# Sheet1.net
KiCad netlist of a schematic drawn in Altium Designer
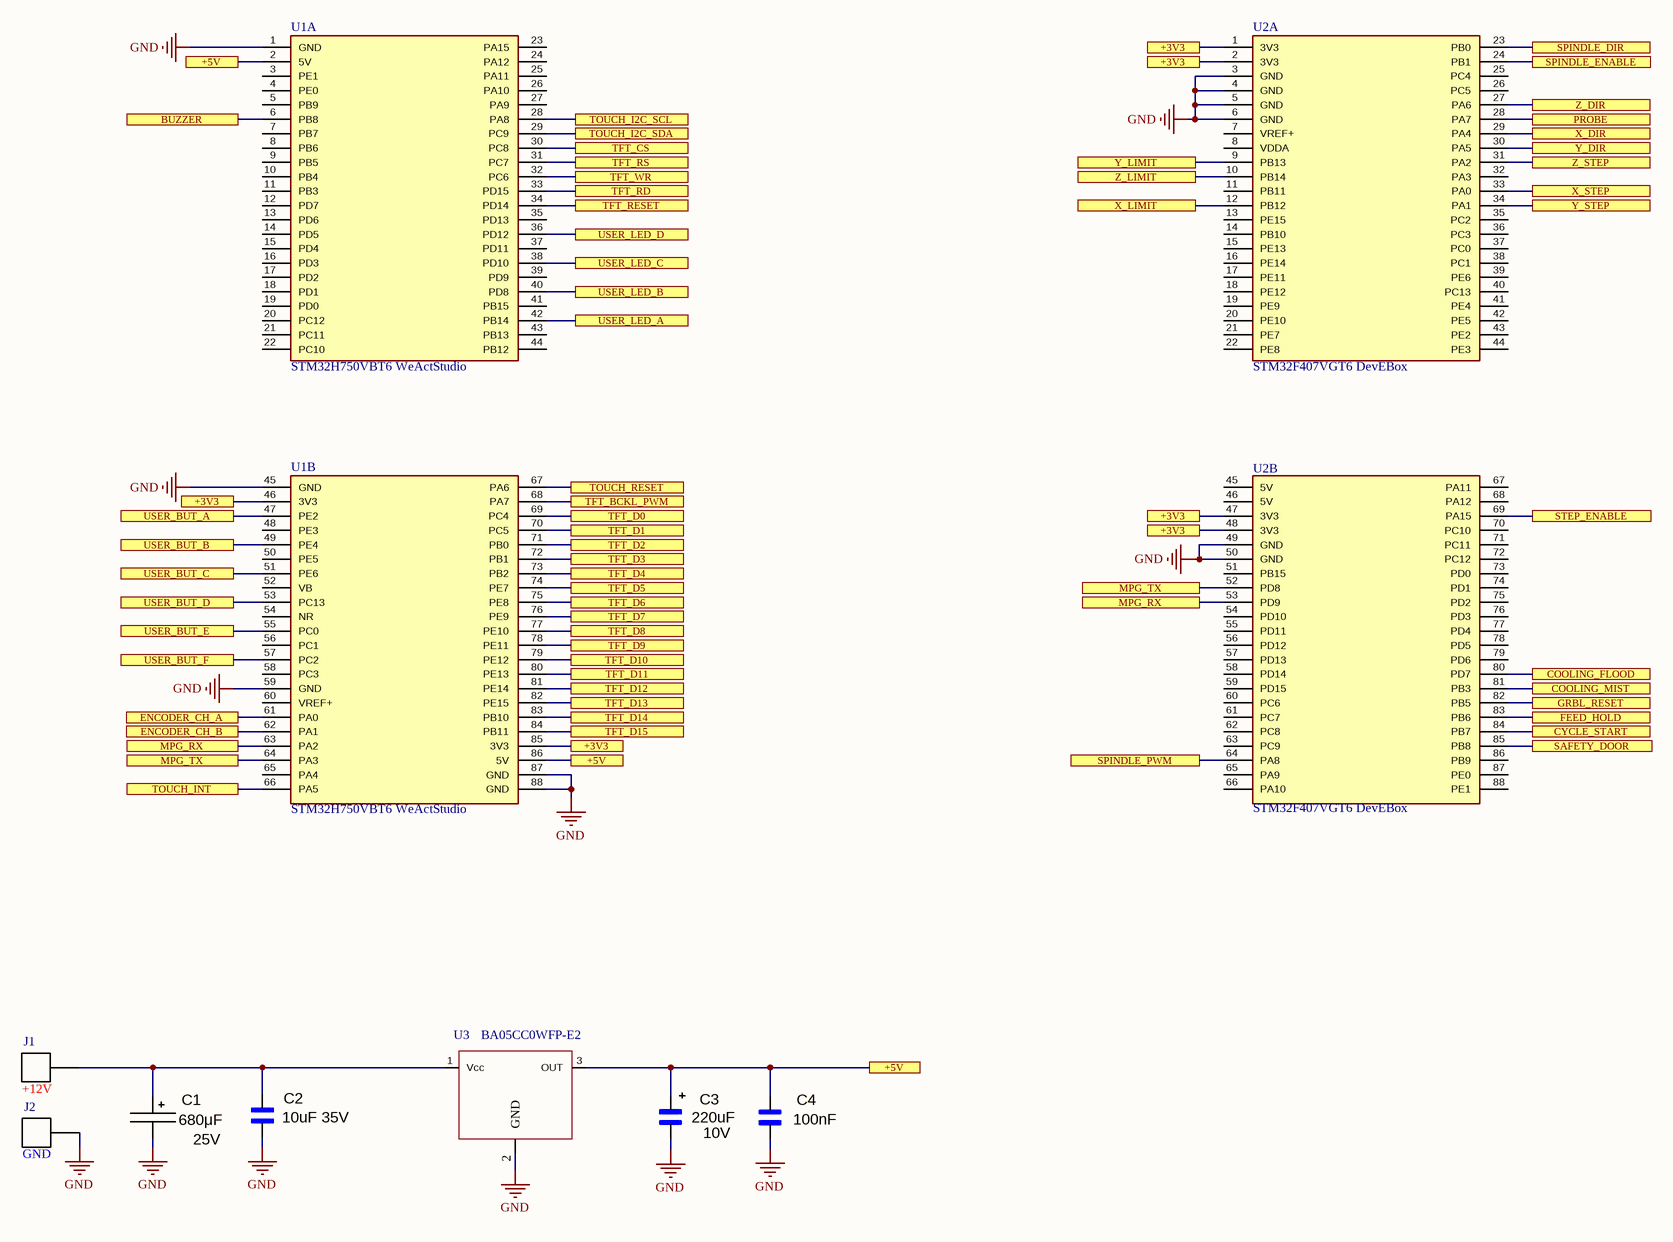
[diagram p0: Sheet1.SchDoc]

(export (version "E")
  (design (tool "Eeschema 10.0.6"))
  (components
    (comp (ref "C1")
      (value "680μF")
      (footprint "CAP 10x16")
      (fields
        (field (name "MANUFACTURER") "FUJICON")
        (field (name "VOLTAGE") "25V")
        (field (name "Comment") "680μF / 25V")
      )
      (libsource (lib "CAN_Library") (part "CAP Aluminium"))
    )
    (comp (ref "C2")
      (value "10uF 35V")
      (footprint "*CAPC3326X230N")
      (description "C1210 10uF 35V X7R")
      (fields (field (name "MANUFACTURER") "SAMSUNG ELECTRO-MECHANICS") (field (name "VOLTAGE") " 35V"))
      (libsource (lib "CAN_Library") (part "CL32B106KLJNNNE"))
    )
    (comp (ref "C3")
      (value "220uF")
      (footprint "SMD 7343-43")
      (description "Cap Tant Solid 220uF 10V E CASE 10% _7.3 X 4.3 X 4mm_ SMD 7343-43 0.1 Ohm 125В°C T/R")
      (fields (field (name "MANUFACTURER") "VISHAY") (field (name "VOLTAGE") "10V"))
      (libsource (lib "CAN_Library") (part "Cap Tant 220uF 10V Case E"))
    )
    (comp (ref "C4")
      (value "100nF")
      (footprint "SMD 0603")
      (description "C1210 10uF 35V X7R")
      (fields (field (name "MANUFACTURER") "SAMSUNG ELECTRO-MECHANICS"))
      (libsource (lib "CAN_Library") (part "CL32B106KLJNNNE"))
    )
    (comp (ref "J1")
      (value "+12V")
      (footprint "Wire")
      (description "Wire")
      (libsource (lib "CAN_Library") (part "Wire"))
    )
    (comp (ref "J2")
      (value "GND")
      (footprint "Wire")
      (description "Wire")
      (libsource (lib "CAN_Library") (part "Wire"))
    )
    (comp (ref "U1")
      (value "STM32H750VBT6 WeActStudio")
      (footprint "WeActStudio STM32H750VBT6")
      (libsource (lib "CAN_Library") (part "STM32H750VBT6 WeActStudio"))
    )
    (comp (ref "U2")
      (value "STM32F407VGT6 DevEBox")
      (footprint "DevEBox V3.0 STM32F407VGT6")
      (libsource (lib "CAN_Library") (part "STM32F407VGT6 DevEBox"))
    )
    (comp (ref "U3")
      (value "BA05CC0WFP-E2")
      (footprint "DPAK228P968X238-4N")
      (description "LDO Regulator")
      (fields (field (name "MANUFACTURER") "ROHM Semiconductor"))
      (libsource (lib "CAN_Library") (part "BA05CC0FP-E2"))
    )
  )
  (nets
    (net (code "1") (name "/+3V3") (class "Default")
      (node (ref "U1") (pin "46") (pinfunction "3V3_46") (pintype "passive"))
      (node (ref "U1") (pin "85") (pinfunction "3V3_85") (pintype "passive"))
      (node (ref "U2") (pin "1") (pinfunction "3V3_1") (pintype "passive"))
      (node (ref "U2") (pin "2") (pinfunction "3V3_2") (pintype "passive"))
      (node (ref "U2") (pin "47") (pinfunction "3V3_47") (pintype "passive"))
      (node (ref "U2") (pin "48") (pinfunction "3V3_48") (pintype "passive"))
    )
    (net (code "2") (name "/+5V") (class "Default")
      (node (ref "C3") (pin "1") (pinfunction "1_1") (pintype "passive"))
      (node (ref "C4") (pin "2") (pinfunction "2_2") (pintype "passive"))
      (node (ref "U1") (pin "2") (pinfunction "5V_2") (pintype "passive"))
      (node (ref "U1") (pin "86") (pinfunction "5V_86") (pintype "passive"))
      (node (ref "U3") (pin "3") (pinfunction "OUT_3") (pintype "passive"))
    )
    (net (code "3") (name "/BUZZER") (class "Default")
      (node (ref "U1") (pin "6") (pinfunction "PB8_6") (pintype "passive"))
    )
    (net (code "4") (name "/COOLING_FLOOD") (class "Default")
      (node (ref "U2") (pin "80") (pinfunction "PD7_80") (pintype "passive"))
    )
    (net (code "5") (name "/COOLING_MIST") (class "Default")
      (node (ref "U2") (pin "81") (pinfunction "PB3_81") (pintype "passive"))
    )
    (net (code "6") (name "/CYCLE_START") (class "Default")
      (node (ref "U2") (pin "84") (pinfunction "PB7_84") (pintype "passive"))
    )
    (net (code "7") (name "/ENCODER_CH_A") (class "Default")
      (node (ref "U1") (pin "61") (pinfunction "PA0_61") (pintype "passive"))
    )
    (net (code "8") (name "/ENCODER_CH_B") (class "Default")
      (node (ref "U1") (pin "62") (pinfunction "PA1_62") (pintype "passive"))
    )
    (net (code "9") (name "/FEED_HOLD") (class "Default")
      (node (ref "U2") (pin "83") (pinfunction "PB6_83") (pintype "passive"))
    )
    (net (code "10") (name "/GRBL_RESET") (class "Default")
      (node (ref "U2") (pin "82") (pinfunction "PB5_82") (pintype "passive"))
    )
    (net (code "11") (name "/MPG_RX") (class "Default")
      (node (ref "U1") (pin "63") (pinfunction "PA2_63") (pintype "passive"))
      (node (ref "U2") (pin "53") (pinfunction "PD9_53") (pintype "passive"))
    )
    (net (code "12") (name "/MPG_TX") (class "Default")
      (node (ref "U1") (pin "64") (pinfunction "PA3_64") (pintype "passive"))
      (node (ref "U2") (pin "52") (pinfunction "PD8_52") (pintype "passive"))
    )
    (net (code "13") (name "/PROBE") (class "Default")
      (node (ref "U2") (pin "28") (pinfunction "PA7_28") (pintype "passive"))
    )
    (net (code "14") (name "/SAFETY_DOOR") (class "Default")
      (node (ref "U2") (pin "85") (pinfunction "PB8_85") (pintype "passive"))
    )
    (net (code "15") (name "/SPINDLE_DIR") (class "Default")
      (node (ref "U2") (pin "23") (pinfunction "PB0_23") (pintype "passive"))
    )
    (net (code "16") (name "/SPINDLE_ENABLE") (class "Default")
      (node (ref "U2") (pin "24") (pinfunction "PB1_24") (pintype "passive"))
    )
    (net (code "17") (name "/SPINDLE_PWM") (class "Default")
      (node (ref "U2") (pin "64") (pinfunction "PA8_64") (pintype "passive"))
    )
    (net (code "18") (name "/STEP_ENABLE") (class "Default")
      (node (ref "U2") (pin "69") (pinfunction "PA15_69") (pintype "passive"))
    )
    (net (code "19") (name "/TFT_BCKL_PWM") (class "Default")
      (node (ref "U1") (pin "68") (pinfunction "PA7_68") (pintype "passive"))
    )
    (net (code "20") (name "/TFT_CS") (class "Default")
      (node (ref "U1") (pin "30") (pinfunction "PC8_30") (pintype "passive"))
    )
    (net (code "21") (name "/TFT_D0") (class "Default")
      (node (ref "U1") (pin "69") (pinfunction "PC4_69") (pintype "passive"))
    )
    (net (code "22") (name "/TFT_D1") (class "Default")
      (node (ref "U1") (pin "70") (pinfunction "PC5_70") (pintype "passive"))
    )
    (net (code "23") (name "/TFT_D2") (class "Default")
      (node (ref "U1") (pin "71") (pinfunction "PB0_71") (pintype "passive"))
    )
    (net (code "24") (name "/TFT_D3") (class "Default")
      (node (ref "U1") (pin "72") (pinfunction "PB1_72") (pintype "passive"))
    )
    (net (code "25") (name "/TFT_D4") (class "Default")
      (node (ref "U1") (pin "73") (pinfunction "PB2_73") (pintype "passive"))
    )
    (net (code "26") (name "/TFT_D5") (class "Default")
      (node (ref "U1") (pin "74") (pinfunction "PE7_74") (pintype "passive"))
    )
    (net (code "27") (name "/TFT_D6") (class "Default")
      (node (ref "U1") (pin "75") (pinfunction "PE8_75") (pintype "passive"))
    )
    (net (code "28") (name "/TFT_D7") (class "Default")
      (node (ref "U1") (pin "76") (pinfunction "PE9_76") (pintype "passive"))
    )
    (net (code "29") (name "/TFT_D8") (class "Default")
      (node (ref "U1") (pin "77") (pinfunction "PE10_77") (pintype "passive"))
    )
    (net (code "30") (name "/TFT_D9") (class "Default")
      (node (ref "U1") (pin "78") (pinfunction "PE11_78") (pintype "passive"))
    )
    (net (code "31") (name "/TFT_D10") (class "Default")
      (node (ref "U1") (pin "79") (pinfunction "PE12_79") (pintype "passive"))
    )
    (net (code "32") (name "/TFT_D11") (class "Default")
      (node (ref "U1") (pin "80") (pinfunction "PE13_80") (pintype "passive"))
    )
    (net (code "33") (name "/TFT_D12") (class "Default")
      (node (ref "U1") (pin "81") (pinfunction "PE14_81") (pintype "passive"))
    )
    (net (code "34") (name "/TFT_D13") (class "Default")
      (node (ref "U1") (pin "82") (pinfunction "PE15_82") (pintype "passive"))
    )
    (net (code "35") (name "/TFT_D14") (class "Default")
      (node (ref "U1") (pin "83") (pinfunction "PB10_83") (pintype "passive"))
    )
    (net (code "36") (name "/TFT_D15") (class "Default")
      (node (ref "U1") (pin "84") (pinfunction "PB11_84") (pintype "passive"))
    )
    (net (code "37") (name "/TFT_RD") (class "Default")
      (node (ref "U1") (pin "33") (pinfunction "PD15_33") (pintype "passive"))
    )
    (net (code "38") (name "/TFT_RESET") (class "Default")
      (node (ref "U1") (pin "34") (pinfunction "PD14_34") (pintype "passive"))
    )
    (net (code "39") (name "/TFT_RS") (class "Default")
      (node (ref "U1") (pin "31") (pinfunction "PC7_31") (pintype "passive"))
    )
    (net (code "40") (name "/TFT_WR") (class "Default")
      (node (ref "U1") (pin "32") (pinfunction "PC6_32") (pintype "passive"))
    )
    (net (code "41") (name "/TOUCH_I2C_SCL") (class "Default")
      (node (ref "U1") (pin "28") (pinfunction "PA8_28") (pintype "passive"))
    )
    (net (code "42") (name "/TOUCH_I2C_SDA") (class "Default")
      (node (ref "U1") (pin "29") (pinfunction "PC9_29") (pintype "passive"))
    )
    (net (code "43") (name "/TOUCH_INT") (class "Default")
      (node (ref "U1") (pin "66") (pinfunction "PA5_66") (pintype "passive"))
    )
    (net (code "44") (name "/TOUCH_RESET") (class "Default")
      (node (ref "U1") (pin "67") (pinfunction "PA6_67") (pintype "passive"))
    )
    (net (code "45") (name "/USER_BUT_A") (class "Default")
      (node (ref "U1") (pin "47") (pinfunction "PE2_47") (pintype "passive"))
    )
    (net (code "46") (name "/USER_BUT_B") (class "Default")
      (node (ref "U1") (pin "49") (pinfunction "PE4_49") (pintype "passive"))
    )
    (net (code "47") (name "/USER_BUT_C") (class "Default")
      (node (ref "U1") (pin "51") (pinfunction "PE6_51") (pintype "passive"))
    )
    (net (code "48") (name "/USER_BUT_D") (class "Default")
      (node (ref "U1") (pin "53") (pinfunction "PC13_53") (pintype "passive"))
    )
    (net (code "49") (name "/USER_BUT_E") (class "Default")
      (node (ref "U1") (pin "55") (pinfunction "PC0_55") (pintype "passive"))
    )
    (net (code "50") (name "/USER_BUT_F") (class "Default")
      (node (ref "U1") (pin "57") (pinfunction "PC2_57") (pintype "passive"))
    )
    (net (code "51") (name "/USER_LED_A") (class "Default")
      (node (ref "U1") (pin "42") (pinfunction "PB14_42") (pintype "passive"))
    )
    (net (code "52") (name "/USER_LED_B") (class "Default")
      (node (ref "U1") (pin "40") (pinfunction "PD8_40") (pintype "passive"))
    )
    (net (code "53") (name "/USER_LED_C") (class "Default")
      (node (ref "U1") (pin "38") (pinfunction "PD10_38") (pintype "passive"))
    )
    (net (code "54") (name "/USER_LED_D") (class "Default")
      (node (ref "U1") (pin "36") (pinfunction "PD12_36") (pintype "passive"))
    )
    (net (code "55") (name "/X_DIR") (class "Default")
      (node (ref "U2") (pin "29") (pinfunction "PA4_29") (pintype "passive"))
    )
    (net (code "56") (name "/X_LIMIT") (class "Default")
      (node (ref "U2") (pin "12") (pinfunction "PB12_12") (pintype "passive"))
    )
    (net (code "57") (name "/X_STEP") (class "Default")
      (node (ref "U2") (pin "33") (pinfunction "PA0_33") (pintype "passive"))
    )
    (net (code "58") (name "/Y_DIR") (class "Default")
      (node (ref "U2") (pin "30") (pinfunction "PA5_30") (pintype "passive"))
    )
    (net (code "59") (name "/Y_LIMIT") (class "Default")
      (node (ref "U2") (pin "9") (pinfunction "PB13_9") (pintype "passive"))
    )
    (net (code "60") (name "/Y_STEP") (class "Default")
      (node (ref "U2") (pin "34") (pinfunction "PA1_34") (pintype "passive"))
    )
    (net (code "61") (name "/Z_DIR") (class "Default")
      (node (ref "U2") (pin "27") (pinfunction "PA6_27") (pintype "passive"))
    )
    (net (code "62") (name "/Z_LIMIT") (class "Default")
      (node (ref "U2") (pin "10") (pinfunction "PB14_10") (pintype "passive"))
    )
    (net (code "63") (name "/Z_STEP") (class "Default")
      (node (ref "U2") (pin "31") (pinfunction "PA2_31") (pintype "passive"))
    )
    (net (code "64") (name "GND") (class "Default")
      (node (ref "C1") (pin "2") (pinfunction "2_2") (pintype "power_in"))
      (node (ref "C2") (pin "1") (pinfunction "1_1") (pintype "passive"))
      (node (ref "C3") (pin "2") (pinfunction "2_2") (pintype "passive"))
      (node (ref "C4") (pin "1") (pinfunction "1_1") (pintype "passive"))
      (node (ref "J2") (pin "1") (pinfunction "1_1") (pintype "passive"))
      (node (ref "U1") (pin "1") (pinfunction "GND_1") (pintype "passive"))
      (node (ref "U1") (pin "45") (pinfunction "GND_45") (pintype "passive"))
      (node (ref "U1") (pin "59") (pinfunction "GND_59") (pintype "passive"))
      (node (ref "U1") (pin "87") (pinfunction "GND_87") (pintype "passive"))
      (node (ref "U1") (pin "88") (pinfunction "GND_88") (pintype "passive"))
      (node (ref "U2") (pin "3") (pinfunction "GND_3") (pintype "passive"))
      (node (ref "U2") (pin "4") (pinfunction "GND_4") (pintype "passive"))
      (node (ref "U2") (pin "49") (pinfunction "GND_49") (pintype "passive"))
      (node (ref "U2") (pin "5") (pinfunction "GND_5") (pintype "passive"))
      (node (ref "U2") (pin "50") (pinfunction "GND_50") (pintype "passive"))
      (node (ref "U2") (pin "6") (pinfunction "GND_6") (pintype "passive"))
      (node (ref "U3") (pin "2") (pinfunction "GND_2") (pintype "passive"))
    )
    (net (code "65") (name "Net-(U3-Vcc)") (class "Default")
      (node (ref "C1") (pin "1") (pinfunction "1_1") (pintype "power_in"))
      (node (ref "C2") (pin "2") (pinfunction "2_2") (pintype "passive"))
      (node (ref "J1") (pin "1") (pinfunction "1_1") (pintype "passive"))
      (node (ref "U3") (pin "1") (pinfunction "Vcc_1") (pintype "power_in"))
    )
    (net (code "66") (name "unconnected-(U1A-PA9-Pad27)") (class "Default")
      (node (ref "U1") (pin "27") (pinfunction "PA9_27") (pintype "passive"))
    )
    (net (code "67") (name "unconnected-(U1A-PA10-Pad26)") (class "Default")
      (node (ref "U1") (pin "26") (pinfunction "PA10_26") (pintype "passive"))
    )
    (net (code "68") (name "unconnected-(U1A-PA11-Pad25)") (class "Default")
      (node (ref "U1") (pin "25") (pinfunction "PA11_25") (pintype "passive"))
    )
    (net (code "69") (name "unconnected-(U1A-PA12-Pad24)") (class "Default")
      (node (ref "U1") (pin "24") (pinfunction "PA12_24") (pintype "passive"))
    )
    (net (code "70") (name "unconnected-(U1A-PA15-Pad23)") (class "Default")
      (node (ref "U1") (pin "23") (pinfunction "PA15_23") (pintype "passive"))
    )
    (net (code "71") (name "unconnected-(U1A-PB3-Pad11)") (class "Default")
      (node (ref "U1") (pin "11") (pinfunction "PB3_11") (pintype "passive"))
    )
    (net (code "72") (name "unconnected-(U1A-PB4-Pad10)") (class "Default")
      (node (ref "U1") (pin "10") (pinfunction "PB4_10") (pintype "passive"))
    )
    (net (code "73") (name "unconnected-(U1A-PB5-Pad9)") (class "Default")
      (node (ref "U1") (pin "9") (pinfunction "PB5_9") (pintype "passive"))
    )
    (net (code "74") (name "unconnected-(U1A-PB6-Pad8)") (class "Default")
      (node (ref "U1") (pin "8") (pinfunction "PB6_8") (pintype "passive"))
    )
    (net (code "75") (name "unconnected-(U1A-PB7-Pad7)") (class "Default")
      (node (ref "U1") (pin "7") (pinfunction "PB7_7") (pintype "passive"))
    )
    (net (code "76") (name "unconnected-(U1A-PB9-Pad5)") (class "Default")
      (node (ref "U1") (pin "5") (pinfunction "PB9_5") (pintype "passive"))
    )
    (net (code "77") (name "unconnected-(U1A-PB12-Pad44)") (class "Default")
      (node (ref "U1") (pin "44") (pinfunction "PB12_44") (pintype "passive"))
    )
    (net (code "78") (name "unconnected-(U1A-PB13-Pad43)") (class "Default")
      (node (ref "U1") (pin "43") (pinfunction "PB13_43") (pintype "passive"))
    )
    (net (code "79") (name "unconnected-(U1A-PB15-Pad41)") (class "Default")
      (node (ref "U1") (pin "41") (pinfunction "PB15_41") (pintype "passive"))
    )
    (net (code "80") (name "unconnected-(U1A-PC10-Pad22)") (class "Default")
      (node (ref "U1") (pin "22") (pinfunction "PC10_22") (pintype "passive"))
    )
    (net (code "81") (name "unconnected-(U1A-PC11-Pad21)") (class "Default")
      (node (ref "U1") (pin "21") (pinfunction "PC11_21") (pintype "passive"))
    )
    (net (code "82") (name "unconnected-(U1A-PC12-Pad20)") (class "Default")
      (node (ref "U1") (pin "20") (pinfunction "PC12_20") (pintype "passive"))
    )
    (net (code "83") (name "unconnected-(U1A-PD0-Pad19)") (class "Default")
      (node (ref "U1") (pin "19") (pinfunction "PD0_19") (pintype "passive"))
    )
    (net (code "84") (name "unconnected-(U1A-PD1-Pad18)") (class "Default")
      (node (ref "U1") (pin "18") (pinfunction "PD1_18") (pintype "passive"))
    )
    (net (code "85") (name "unconnected-(U1A-PD2-Pad17)") (class "Default")
      (node (ref "U1") (pin "17") (pinfunction "PD2_17") (pintype "passive"))
    )
    (net (code "86") (name "unconnected-(U1A-PD3-Pad16)") (class "Default")
      (node (ref "U1") (pin "16") (pinfunction "PD3_16") (pintype "passive"))
    )
    (net (code "87") (name "unconnected-(U1A-PD4-Pad15)") (class "Default")
      (node (ref "U1") (pin "15") (pinfunction "PD4_15") (pintype "passive"))
    )
    (net (code "88") (name "unconnected-(U1A-PD5-Pad14)") (class "Default")
      (node (ref "U1") (pin "14") (pinfunction "PD5_14") (pintype "passive"))
    )
    (net (code "89") (name "unconnected-(U1A-PD6-Pad13)") (class "Default")
      (node (ref "U1") (pin "13") (pinfunction "PD6_13") (pintype "passive"))
    )
    (net (code "90") (name "unconnected-(U1A-PD7-Pad12)") (class "Default")
      (node (ref "U1") (pin "12") (pinfunction "PD7_12") (pintype "passive"))
    )
    (net (code "91") (name "unconnected-(U1A-PD9-Pad39)") (class "Default")
      (node (ref "U1") (pin "39") (pinfunction "PD9_39") (pintype "passive"))
    )
    (net (code "92") (name "unconnected-(U1A-PD11-Pad37)") (class "Default")
      (node (ref "U1") (pin "37") (pinfunction "PD11_37") (pintype "passive"))
    )
    (net (code "93") (name "unconnected-(U1A-PD13-Pad35)") (class "Default")
      (node (ref "U1") (pin "35") (pinfunction "PD13_35") (pintype "passive"))
    )
    (net (code "94") (name "unconnected-(U1A-PE0-Pad4)") (class "Default")
      (node (ref "U1") (pin "4") (pinfunction "PE0_4") (pintype "passive"))
    )
    (net (code "95") (name "unconnected-(U1A-PE1-Pad3)") (class "Default")
      (node (ref "U1") (pin "3") (pinfunction "PE1_3") (pintype "passive"))
    )
    (net (code "96") (name "unconnected-(U1B-NR-Pad54)") (class "Default")
      (node (ref "U1") (pin "54") (pinfunction "NR_54") (pintype "passive"))
    )
    (net (code "97") (name "unconnected-(U1B-PA4-Pad65)") (class "Default")
      (node (ref "U1") (pin "65") (pinfunction "PA4_65") (pintype "passive"))
    )
    (net (code "98") (name "unconnected-(U1B-PC1-Pad56)") (class "Default")
      (node (ref "U1") (pin "56") (pinfunction "PC1_56") (pintype "passive"))
    )
    (net (code "99") (name "unconnected-(U1B-PC3-Pad58)") (class "Default")
      (node (ref "U1") (pin "58") (pinfunction "PC3_58") (pintype "passive"))
    )
    (net (code "100") (name "unconnected-(U1B-PE3-Pad48)") (class "Default")
      (node (ref "U1") (pin "48") (pinfunction "PE3_48") (pintype "passive"))
    )
    (net (code "101") (name "unconnected-(U1B-PE5-Pad50)") (class "Default")
      (node (ref "U1") (pin "50") (pinfunction "PE5_50") (pintype "passive"))
    )
    (net (code "102") (name "unconnected-(U1B-VB-Pad52)") (class "Default")
      (node (ref "U1") (pin "52") (pinfunction "VB_52") (pintype "passive"))
    )
    (net (code "103") (name "unconnected-(U1B-VREF+-Pad60)") (class "Default")
      (node (ref "U1") (pin "60") (pinfunction "VREF+_60") (pintype "passive"))
    )
    (net (code "104") (name "unconnected-(U2A-PA3-Pad32)") (class "Default")
      (node (ref "U2") (pin "32") (pinfunction "PA3_32") (pintype "passive"))
    )
    (net (code "105") (name "unconnected-(U2A-PB10-Pad14)") (class "Default")
      (node (ref "U2") (pin "14") (pinfunction "PB10_14") (pintype "passive"))
    )
    (net (code "106") (name "unconnected-(U2A-PB11-Pad11)") (class "Default")
      (node (ref "U2") (pin "11") (pinfunction "PB11_11") (pintype "passive"))
    )
    (net (code "107") (name "unconnected-(U2A-PC0-Pad37)") (class "Default")
      (node (ref "U2") (pin "37") (pinfunction "PC0_37") (pintype "passive"))
    )
    (net (code "108") (name "unconnected-(U2A-PC1-Pad38)") (class "Default")
      (node (ref "U2") (pin "38") (pinfunction "PC1_38") (pintype "passive"))
    )
    (net (code "109") (name "unconnected-(U2A-PC2-Pad35)") (class "Default")
      (node (ref "U2") (pin "35") (pinfunction "PC2_35") (pintype "passive"))
    )
    (net (code "110") (name "unconnected-(U2A-PC3-Pad36)") (class "Default")
      (node (ref "U2") (pin "36") (pinfunction "PC3_36") (pintype "passive"))
    )
    (net (code "111") (name "unconnected-(U2A-PC4-Pad25)") (class "Default")
      (node (ref "U2") (pin "25") (pinfunction "PC4_25") (pintype "passive"))
    )
    (net (code "112") (name "unconnected-(U2A-PC5-Pad26)") (class "Default")
      (node (ref "U2") (pin "26") (pinfunction "PC5_26") (pintype "passive"))
    )
    (net (code "113") (name "unconnected-(U2A-PC13-Pad40)") (class "Default")
      (node (ref "U2") (pin "40") (pinfunction "PC13_40") (pintype "passive"))
    )
    (net (code "114") (name "unconnected-(U2A-PE2-Pad43)") (class "Default")
      (node (ref "U2") (pin "43") (pinfunction "PE2_43") (pintype "passive"))
    )
    (net (code "115") (name "unconnected-(U2A-PE3-Pad44)") (class "Default")
      (node (ref "U2") (pin "44") (pinfunction "PE3_44") (pintype "passive"))
    )
    (net (code "116") (name "unconnected-(U2A-PE4-Pad41)") (class "Default")
      (node (ref "U2") (pin "41") (pinfunction "PE4_41") (pintype "passive"))
    )
    (net (code "117") (name "unconnected-(U2A-PE5-Pad42)") (class "Default")
      (node (ref "U2") (pin "42") (pinfunction "PE5_42") (pintype "passive"))
    )
    (net (code "118") (name "unconnected-(U2A-PE6-Pad39)") (class "Default")
      (node (ref "U2") (pin "39") (pinfunction "PE6_39") (pintype "passive"))
    )
    (net (code "119") (name "unconnected-(U2A-PE7-Pad21)") (class "Default")
      (node (ref "U2") (pin "21") (pinfunction "PE7_21") (pintype "passive"))
    )
    (net (code "120") (name "unconnected-(U2A-PE8-Pad22)") (class "Default")
      (node (ref "U2") (pin "22") (pinfunction "PE8_22") (pintype "passive"))
    )
    (net (code "121") (name "unconnected-(U2A-PE9-Pad19)") (class "Default")
      (node (ref "U2") (pin "19") (pinfunction "PE9_19") (pintype "passive"))
    )
    (net (code "122") (name "unconnected-(U2A-PE10-Pad20)") (class "Default")
      (node (ref "U2") (pin "20") (pinfunction "PE10_20") (pintype "passive"))
    )
    (net (code "123") (name "unconnected-(U2A-PE11-Pad17)") (class "Default")
      (node (ref "U2") (pin "17") (pinfunction "PE11_17") (pintype "passive"))
    )
    (net (code "124") (name "unconnected-(U2A-PE12-Pad18)") (class "Default")
      (node (ref "U2") (pin "18") (pinfunction "PE12_18") (pintype "passive"))
    )
    (net (code "125") (name "unconnected-(U2A-PE13-Pad15)") (class "Default")
      (node (ref "U2") (pin "15") (pinfunction "PE13_15") (pintype "passive"))
    )
    (net (code "126") (name "unconnected-(U2A-PE14-Pad16)") (class "Default")
      (node (ref "U2") (pin "16") (pinfunction "PE14_16") (pintype "passive"))
    )
    (net (code "127") (name "unconnected-(U2A-PE15-Pad13)") (class "Default")
      (node (ref "U2") (pin "13") (pinfunction "PE15_13") (pintype "passive"))
    )
    (net (code "128") (name "unconnected-(U2A-VDDA-Pad8)") (class "Default")
      (node (ref "U2") (pin "8") (pinfunction "VDDA_8") (pintype "passive"))
    )
    (net (code "129") (name "unconnected-(U2A-VREF+-Pad7)") (class "Default")
      (node (ref "U2") (pin "7") (pinfunction "VREF+_7") (pintype "passive"))
    )
    (net (code "130") (name "unconnected-(U2B-5V-Pad45)") (class "Default")
      (node (ref "U2") (pin "45") (pinfunction "5V_45") (pintype "passive"))
    )
    (net (code "131") (name "unconnected-(U2B-5V-Pad46)") (class "Default")
      (node (ref "U2") (pin "46") (pinfunction "5V_46") (pintype "passive"))
    )
    (net (code "132") (name "unconnected-(U2B-PA9-Pad65)") (class "Default")
      (node (ref "U2") (pin "65") (pinfunction "PA9_65") (pintype "passive"))
    )
    (net (code "133") (name "unconnected-(U2B-PA10-Pad66)") (class "Default")
      (node (ref "U2") (pin "66") (pinfunction "PA10_66") (pintype "passive"))
    )
    (net (code "134") (name "unconnected-(U2B-PA11-Pad67)") (class "Default")
      (node (ref "U2") (pin "67") (pinfunction "PA11_67") (pintype "passive"))
    )
    (net (code "135") (name "unconnected-(U2B-PA12-Pad68)") (class "Default")
      (node (ref "U2") (pin "68") (pinfunction "PA12_68") (pintype "passive"))
    )
    (net (code "136") (name "unconnected-(U2B-PB9-Pad86)") (class "Default")
      (node (ref "U2") (pin "86") (pinfunction "PB9_86") (pintype "passive"))
    )
    (net (code "137") (name "unconnected-(U2B-PB15-Pad51)") (class "Default")
      (node (ref "U2") (pin "51") (pinfunction "PB15_51") (pintype "passive"))
    )
    (net (code "138") (name "unconnected-(U2B-PC6-Pad60)") (class "Default")
      (node (ref "U2") (pin "60") (pinfunction "PC6_60") (pintype "passive"))
    )
    (net (code "139") (name "unconnected-(U2B-PC7-Pad61)") (class "Default")
      (node (ref "U2") (pin "61") (pinfunction "PC7_61") (pintype "passive"))
    )
    (net (code "140") (name "unconnected-(U2B-PC8-Pad62)") (class "Default")
      (node (ref "U2") (pin "62") (pinfunction "PC8_62") (pintype "passive"))
    )
    (net (code "141") (name "unconnected-(U2B-PC9-Pad63)") (class "Default")
      (node (ref "U2") (pin "63") (pinfunction "PC9_63") (pintype "passive"))
    )
    (net (code "142") (name "unconnected-(U2B-PC10-Pad70)") (class "Default")
      (node (ref "U2") (pin "70") (pinfunction "PC10_70") (pintype "passive"))
    )
    (net (code "143") (name "unconnected-(U2B-PC11-Pad71)") (class "Default")
      (node (ref "U2") (pin "71") (pinfunction "PC11_71") (pintype "passive"))
    )
    (net (code "144") (name "unconnected-(U2B-PC12-Pad72)") (class "Default")
      (node (ref "U2") (pin "72") (pinfunction "PC12_72") (pintype "passive"))
    )
    (net (code "145") (name "unconnected-(U2B-PD0-Pad73)") (class "Default")
      (node (ref "U2") (pin "73") (pinfunction "PD0_73") (pintype "passive"))
    )
    (net (code "146") (name "unconnected-(U2B-PD1-Pad74)") (class "Default")
      (node (ref "U2") (pin "74") (pinfunction "PD1_74") (pintype "passive"))
    )
    (net (code "147") (name "unconnected-(U2B-PD2-Pad75)") (class "Default")
      (node (ref "U2") (pin "75") (pinfunction "PD2_75") (pintype "passive"))
    )
    (net (code "148") (name "unconnected-(U2B-PD3-Pad76)") (class "Default")
      (node (ref "U2") (pin "76") (pinfunction "PD3_76") (pintype "passive"))
    )
    (net (code "149") (name "unconnected-(U2B-PD4-Pad77)") (class "Default")
      (node (ref "U2") (pin "77") (pinfunction "PD4_77") (pintype "passive"))
    )
    (net (code "150") (name "unconnected-(U2B-PD5-Pad78)") (class "Default")
      (node (ref "U2") (pin "78") (pinfunction "PD5_78") (pintype "passive"))
    )
    (net (code "151") (name "unconnected-(U2B-PD6-Pad79)") (class "Default")
      (node (ref "U2") (pin "79") (pinfunction "PD6_79") (pintype "passive"))
    )
    (net (code "152") (name "unconnected-(U2B-PD10-Pad54)") (class "Default")
      (node (ref "U2") (pin "54") (pinfunction "PD10_54") (pintype "passive"))
    )
    (net (code "153") (name "unconnected-(U2B-PD11-Pad55)") (class "Default")
      (node (ref "U2") (pin "55") (pinfunction "PD11_55") (pintype "passive"))
    )
    (net (code "154") (name "unconnected-(U2B-PD12-Pad56)") (class "Default")
      (node (ref "U2") (pin "56") (pinfunction "PD12_56") (pintype "passive"))
    )
    (net (code "155") (name "unconnected-(U2B-PD13-Pad57)") (class "Default")
      (node (ref "U2") (pin "57") (pinfunction "PD13_57") (pintype "passive"))
    )
    (net (code "156") (name "unconnected-(U2B-PD14-Pad58)") (class "Default")
      (node (ref "U2") (pin "58") (pinfunction "PD14_58") (pintype "passive"))
    )
    (net (code "157") (name "unconnected-(U2B-PD15-Pad59)") (class "Default")
      (node (ref "U2") (pin "59") (pinfunction "PD15_59") (pintype "passive"))
    )
    (net (code "158") (name "unconnected-(U2B-PE0-Pad87)") (class "Default")
      (node (ref "U2") (pin "87") (pinfunction "PE0_87") (pintype "passive"))
    )
    (net (code "159") (name "unconnected-(U2B-PE1-Pad88)") (class "Default")
      (node (ref "U2") (pin "88") (pinfunction "PE1_88") (pintype "passive"))
    )
  )
)
